# battery_diode-charging.net
KiCad netlist of a schematic drawn in Altium Designer
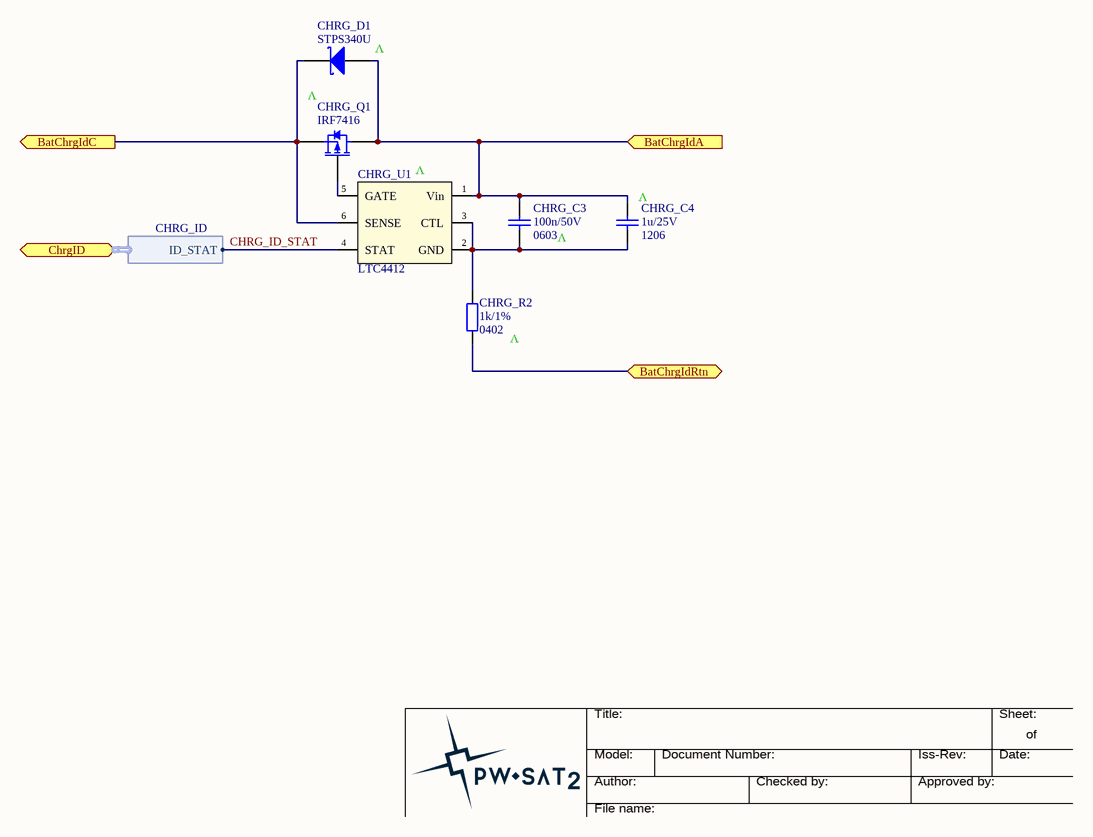
[diagram p0: battery_diode-charging.SchDoc]

(export (version "E")
  (design (tool "Eeschema 10.0.6"))
  (components
    (comp (ref "CHRG_C3")
      (value "100n/50V")
      (footprint "SMD_Capacitor_0603")
      (description "Ceramic Cap Murata Automotive 100n/50V X7R 0603")
      (fields
        (field (name "MANUFACTURER") "Murata")
        (field (name "MANUFACTURERPARTNUMBER") "GCJ188R71H104KA12D")
        (field (name "PACKAGE") "0603")
      )
      (libsource (lib "capacitors") (part "Cer_GCJ188R71H104KA12D"))
    )
    (comp (ref "CHRG_C4")
      (value "1u/25V")
      (footprint "SMD_Capacitor_1206")
      (description "Ceramic Cap Kemet COTS 1u/25V X7R 1206")
      (fields
        (field (name "MANUFACTURERPARTNUMBER") "C1206T105K3RALTU")
        (field (name "MANUFACTURER") "Kemet")
        (field (name "PACKAGE") "1206")
      )
      (libsource (lib "capacitors") (part "Cer_C1206T105K3RALTU"))
    )
    (comp (ref "CHRG_D1")
      (value "STPS340U")
      (footprint "DO-214AA")
      (description "3A/40V Power Schottky Rectifier.")
      (fields (field (name "MANUFACTURER") "STMicroelectronics"))
      (libsource (lib "diodes") (part "STPS340x"))
    )
    (comp (ref "CHRG_Q1")
      (value "IRF7416")
      (footprint "SOIC-8-N_SSSGDDDD")
      (description "10A/30V HEXFET Power P-MOSFET.")
      (fields (field (name "MANUFACTURER") "International Rectifier"))
      (libsource (lib "transistors") (part "IRF7416"))
    )
    (comp (ref "CHRG_R2")
      (value "1k/1%")
      (footprint "SMD_Resistor_0402")
      (description "1k/1% Vishay CRCW 0402 Resistor. 63mW, 100ppm, 50V.")
      (fields
        (field (name "MANUFACTURER") "Vishay")
        (field (name "MANUFACTURERPARTNUMBER") "CRCW04021K00FKxxxx")
        (field (name "PACKAGE") "0402")
      )
      (libsource (lib "resistors") (part "CRCW04021K00FKxxxx"))
    )
    (comp (ref "CHRG_U1")
      (value "LTC4412")
      (footprint "SOT23-6")
      (description "Ideal Diode, Low Loss PowerPath Controller.")
      (fields (field (name "MANUFACTURER") "Linear Technology"))
      (libsource (lib "microcircuits") (part "LTC4412"))
    )
  )
  (nets
    (net (code "2") (name "/BatChrgIdA") (class "Default")
      (node (ref "CHRG_C3") (pin "1") (pinfunction "1_1") (pintype "passive"))
      (node (ref "CHRG_C4") (pin "1") (pinfunction "1_1") (pintype "passive"))
      (node (ref "CHRG_D1") (pin "A") (pinfunction "A_A") (pintype "passive"))
      (node (ref "CHRG_Q1") (pin "D") (pinfunction "D_D") (pintype "passive"))
      (node (ref "CHRG_U1") (pin "1") (pinfunction "Vin_1") (pintype "passive"))
    )
    (net (code "3") (name "/BatChrgIdC") (class "Default")
      (node (ref "CHRG_D1") (pin "K") (pinfunction "K_K") (pintype "passive"))
      (node (ref "CHRG_Q1") (pin "S") (pinfunction "S_S") (pintype "passive"))
      (node (ref "CHRG_U1") (pin "6") (pinfunction "SENSE_6") (pintype "passive"))
    )
    (net (code "4") (name "/BatChrgIdRtn") (class "Default")
      (node (ref "CHRG_R2") (pin "2") (pinfunction "2_2") (pintype "passive"))
    )
    (net (code "5") (name "/CHRG_ID_STAT") (class "Default")
      (node (ref "CHRG_U1") (pin "4") (pinfunction "STAT_4") (pintype "passive"))
    )
    (net (code "7") (name "Net-(CHRG_U1-CTL)") (class "Default")
      (node (ref "CHRG_C3") (pin "2") (pinfunction "2_2") (pintype "passive"))
      (node (ref "CHRG_C4") (pin "2") (pinfunction "2_2") (pintype "passive"))
      (node (ref "CHRG_R2") (pin "1") (pinfunction "1_1") (pintype "passive"))
      (node (ref "CHRG_U1") (pin "2") (pinfunction "GND_2") (pintype "passive"))
      (node (ref "CHRG_U1") (pin "3") (pinfunction "CTL_3") (pintype "passive"))
    )
    (net (code "8") (name "Net-(CHRG_U1-GATE)") (class "Default")
      (node (ref "CHRG_Q1") (pin "G") (pinfunction "G_G") (pintype "passive"))
      (node (ref "CHRG_U1") (pin "5") (pinfunction "GATE_5") (pintype "passive"))
    )
  )
)
